# switch_profet_btt62001.net
KiCad netlist of a schematic drawn in Altium Designer
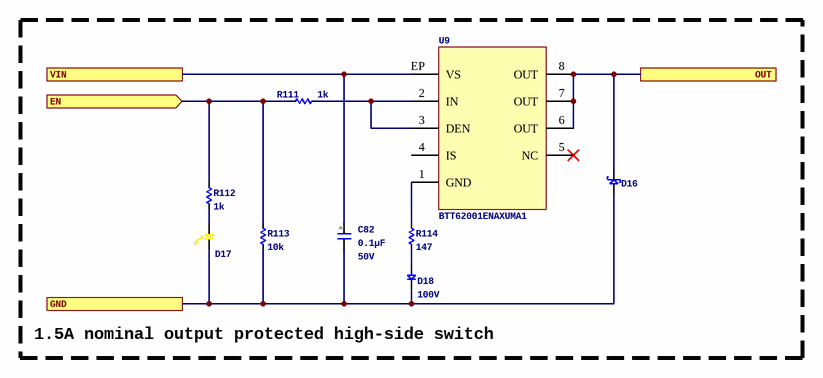
[diagram p0: switch_profet_btt62001.SchDoc]

(export (version "E")
  (design (tool "Eeschema 10.0.6"))
  (components
    (comp (ref "C82")
      (value "CGA2B3X7R1H104M050BB")
      (footprint "C0402_0.55MM")
      (description "CAP CER 0.1UF 50V X7R 0402")
      (fields
        (field (name "CAPACITANCE") "0.1µF")
        (field (name "VOLTAGE - RATED") "50V")
        (field (name "TOLERANCE") "±20%")
        (field (name "MANUFACTURER") "TDK Corporation")
      )
      (libsource (lib "sscp") (part "__template_cap_auto"))
    )
    (comp (ref "D16")
      (value "15MQ040NPBF")
      (footprint "SMA")
      (description "DIODE SCHOTTKY 40V 3A SMA")
      (fields (field (name "MANUFACTURER") "Vishay Semiconductor Diodes Division"))
      (libsource (lib "SSCP") (part "SCHOTTKY_15MQ040NPBF"))
    )
    (comp (ref "D17")
      (value "LTST-C190YKT")
      (footprint "LED_0603P_YELLOW")
      (description "LED YELLOW CLEAR 0603 SMD")
      (fields (field (name "MANUFACTURER") "Lite-On Inc"))
      (libsource (lib "SSCP") (part "LED_0603_YELLOW_LTST-C190YKT"))
    )
    (comp (ref "D18")
      (value "1N4148W-TP")
      (footprint "SOD123")
      (description "DIODE SWITCH 100V 150MA SOD123")
      (fields
        (field (name "MANUFACTURER") "Micro Commercial Co")
        (field (name "VOLTAGE - DC REVERSE (VR) (MAX)") "100V")
      )
      (libsource (lib "SSCP") (part "DIODE_1N4148WTPMSTR"))
    )
    (comp (ref "R111")
      (value "~")
      (footprint "R0402_0.40MM")
      (description "RES SMD 1K OHM 1% 1/10W 0402")
      (fields (field (name "RESISTANCE") "1k") (field (name "TOLERANCE") "±1%"))
      (libsource (lib "sscp") (part "__template_resistor"))
    )
    (comp (ref "R112")
      (value "ERJ-2RKF1001X")
      (footprint "R0402_0.40MM")
      (description "RES SMD 1K OHM 1% 1/10W 0402")
      (fields
        (field (name "RESISTANCE") "1k")
        (field (name "TOLERANCE") "±1%")
        (field (name "MANUFACTURER") "Panasonic Electronic Components")
      )
      (libsource (lib "sscp") (part "__template_resistor"))
    )
    (comp (ref "R113")
      (value "~")
      (footprint "R0402_0.40MM")
      (description "RES SMD 10K OHM 1% 1/10W 0402")
      (fields (field (name "RESISTANCE") "10k") (field (name "TOLERANCE") "±1%"))
      (libsource (lib "sscp") (part "__template_resistor"))
    )
    (comp (ref "R114")
      (value "ERJ-2RKF1470X")
      (footprint "R0402_0.40MM")
      (description "RES SMD 147 OHM 1% 1/10W 0402")
      (fields
        (field (name "RESISTANCE") "147")
        (field (name "TOLERANCE") "±1%")
        (field (name "MANUFACTURER") "Panasonic Electronic Components")
      )
      (libsource (lib "sscp") (part "__template_resistor"))
    )
    (comp (ref "U9")
      (value "BTT62001ENAXUMA1")
      (footprint "PG-TDSO-8-31")
      (description "1.5 amp high side load driver")
      (fields (field (name "MANUFACTURER") "Infineon"))
      (libsource (lib "SSCP") (part "PROFET_BTT62001ENAXUMA1"))
    )
  )
  (nets
    (net (code "1") (name "/EN") (class "Default")
      (node (ref "R111") (pin "2") (pintype "passive"))
      (node (ref "R112") (pin "2") (pintype "passive"))
      (node (ref "R113") (pin "2") (pintype "passive"))
    )
    (net (code "2") (name "/GND") (class "Default")
      (node (ref "C82") (pin "2") (pintype "passive"))
      (node (ref "D16") (pin "1") (pintype "passive"))
      (node (ref "D17") (pin "1") (pintype "passive"))
      (node (ref "D18") (pin "2") (pintype "passive"))
      (node (ref "R113") (pin "1") (pintype "passive"))
    )
    (net (code "3") (name "/OUT") (class "Default")
      (node (ref "D16") (pin "2") (pintype "passive"))
      (node (ref "U9") (pin "6") (pinfunction "OUT_6") (pintype "passive"))
      (node (ref "U9") (pin "7") (pinfunction "OUT_7") (pintype "passive"))
      (node (ref "U9") (pin "8") (pinfunction "OUT_8") (pintype "passive"))
    )
    (net (code "4") (name "/VIN") (class "Default")
      (node (ref "C82") (pin "1") (pintype "passive"))
      (node (ref "U9") (pin "EP") (pinfunction "VS_EP") (pintype "passive"))
    )
    (net (code "5") (name "Net-(D17-Pad2)") (class "Default")
      (node (ref "D17") (pin "2") (pintype "passive"))
      (node (ref "R112") (pin "1") (pintype "passive"))
    )
    (net (code "6") (name "Net-(D18-Pad1)") (class "Default")
      (node (ref "D18") (pin "1") (pintype "passive"))
      (node (ref "R114") (pin "1") (pintype "passive"))
    )
    (net (code "7") (name "Net-(U9-DEN)") (class "Default")
      (node (ref "R111") (pin "1") (pintype "passive"))
      (node (ref "U9") (pin "2") (pinfunction "IN_2") (pintype "passive"))
      (node (ref "U9") (pin "3") (pinfunction "DEN_3") (pintype "passive"))
    )
    (net (code "8") (name "Net-(U9-GND)") (class "Default")
      (node (ref "R114") (pin "2") (pintype "passive"))
      (node (ref "U9") (pin "1") (pinfunction "GND_1") (pintype "passive"))
    )
    (net (code "9") (name "unconnected-(U9-IS-Pad4)") (class "Default")
      (node (ref "U9") (pin "4") (pinfunction "IS_4") (pintype "passive"))
    )
    (net (code "10") (name "unconnected-(U9-NC-Pad5)") (class "Default")
      (node (ref "U9") (pin "5") (pinfunction "NC_5") (pintype "passive+no_connect"))
    )
  )
)
